# PumpMonitoring.net
KiCad netlist of a schematic drawn in EAGLE
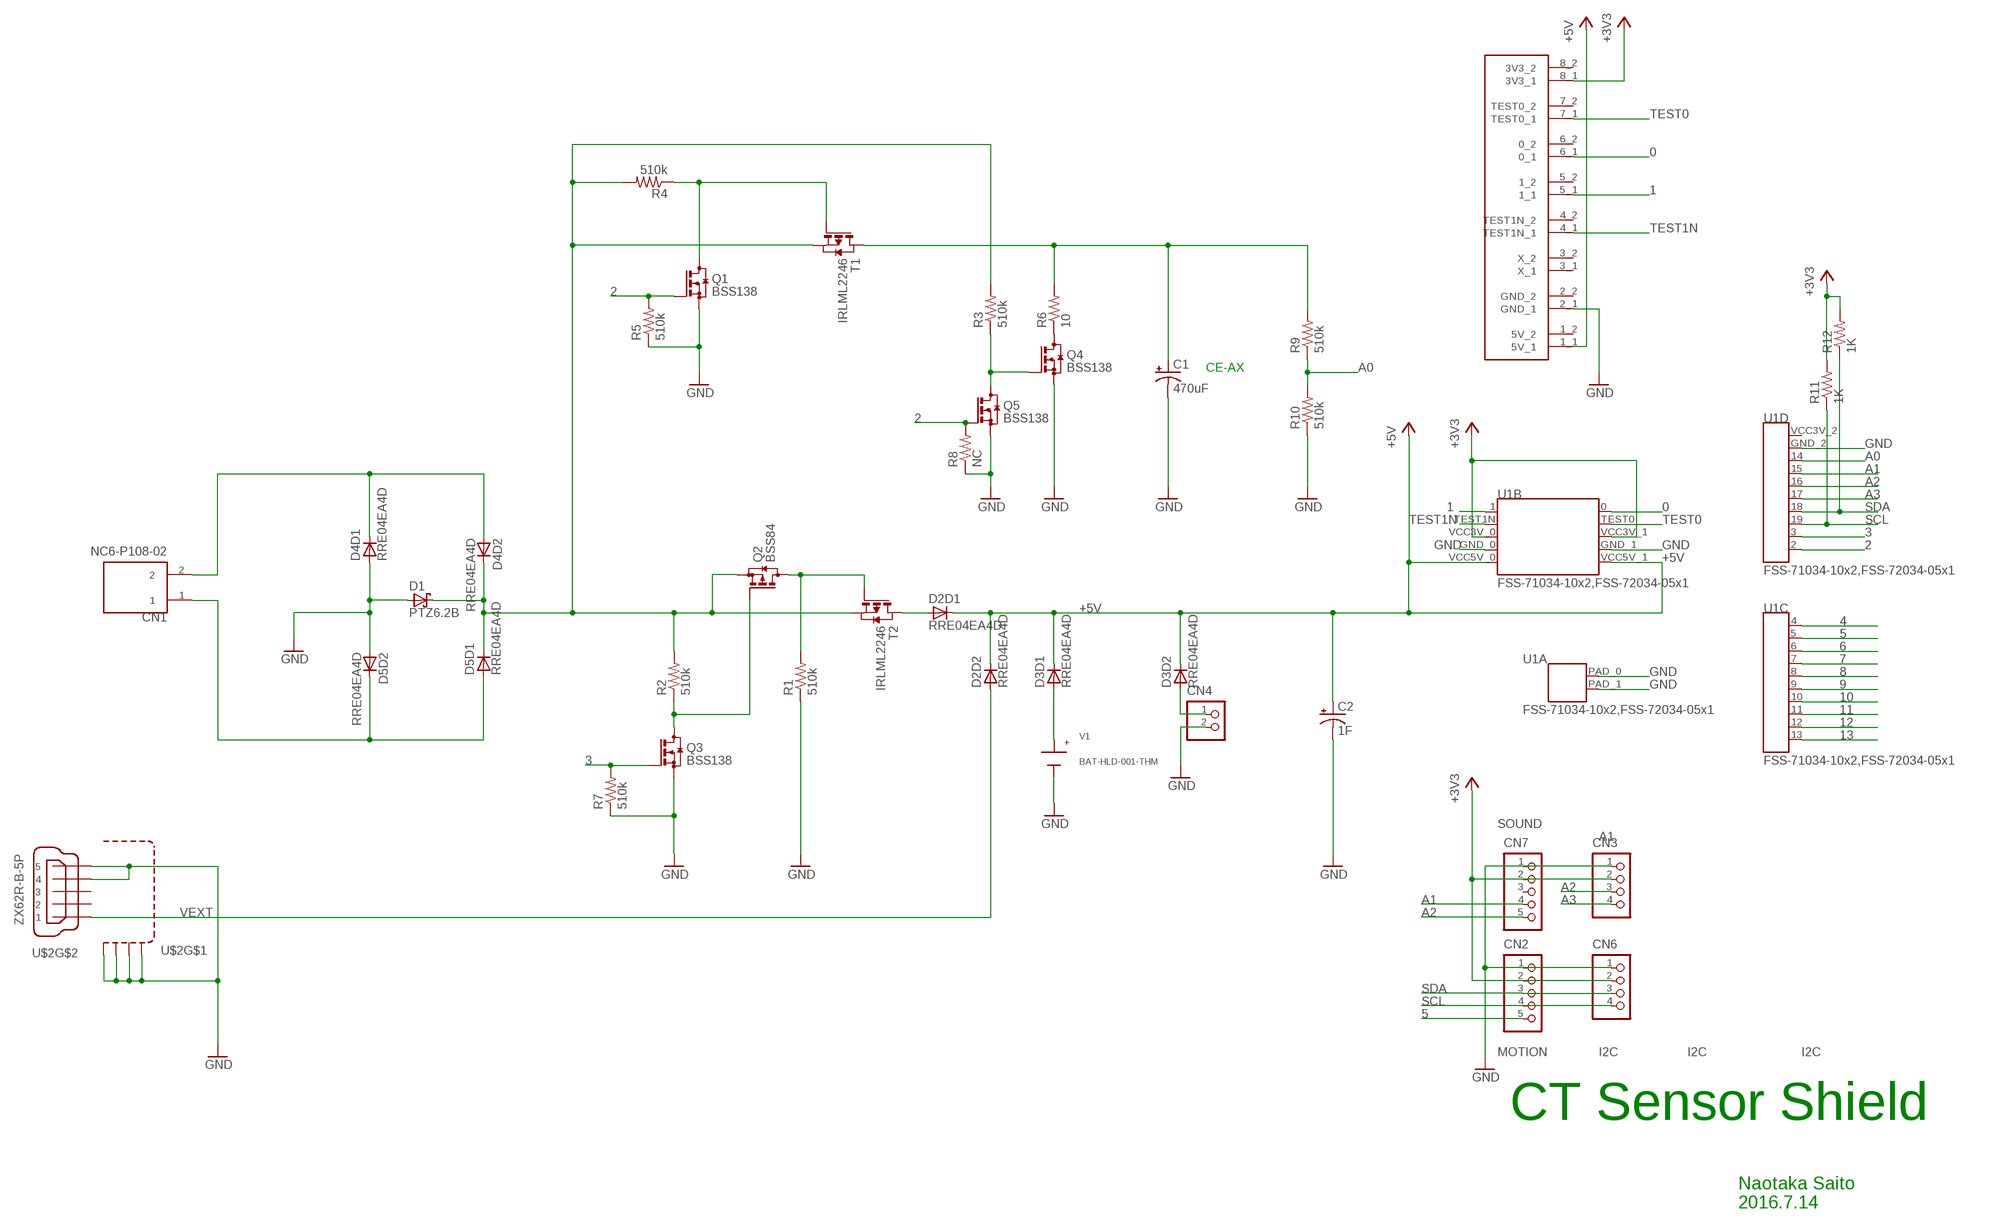
[diagram p0: schematic, sheet 1]

(export (version "E")
  (design (tool "Eeschema 10.0.6"))
  (components
    (comp (ref "C1")
      (value "470uF")
      (footprint "eagle-import:E5-10,5")
      (libsource (lib "eagle-import") (part "CPOL-USE5-10.5"))
    )
    (comp (ref "C2")
      (value "1F")
      (footprint "eagle-import:E5-20")
      (libsource (lib "eagle-import") (part "CPOL-USE5-20"))
    )
    (comp (ref "CN1")
      (value "NC6-P108-02")
      (footprint "eagle-import:2PIN")
      (libsource (lib "eagle-import") (part "TE-NC6-P108-02"))
    )
    (comp (ref "CN2")
      (value "B5B-PH-K-S")
      (footprint "eagle-import:B5B-PH-K-S")
      (libsource (lib "eagle-import") (part "B5B-PH-K-S"))
    )
    (comp (ref "CN3")
      (value "B4B-PH-K-S")
      (footprint "eagle-import:B4B-PH-K-S")
      (libsource (lib "eagle-import") (part "B4B-PH-K-S"))
    )
    (comp (ref "CN4")
      (value "B2B-PH-K-S")
      (footprint "eagle-import:B2B-PH-K-S")
      (libsource (lib "eagle-import") (part "B2B-PH-K-S"))
    )
    (comp (ref "CN6")
      (value "B4B-PH-K-S")
      (footprint "eagle-import:B4B-PH-K-S")
      (libsource (lib "eagle-import") (part "B4B-PH-K-S"))
    )
    (comp (ref "CN7")
      (value "B5B-PH-K-S")
      (footprint "eagle-import:B5B-PH-K-S")
      (libsource (lib "eagle-import") (part "B5B-PH-K-S"))
    )
    (comp (ref "D1")
      (value "PTZ6.2B")
      (footprint "eagle-import:DO214AC")
      (libsource (lib "eagle-import") (part "PTZXXB"))
    )
    (comp (ref "D2")
      (value "RRE04EA4D")
      (footprint "eagle-import:TSMD5")
      (libsource (lib "eagle-import") (part "RRE04EA4D"))
    )
    (comp (ref "D3")
      (value "RRE04EA4D")
      (footprint "eagle-import:TSMD5")
      (libsource (lib "eagle-import") (part "RRE04EA4D"))
    )
    (comp (ref "D4")
      (value "RRE04EA4D")
      (footprint "eagle-import:TSMD5")
      (libsource (lib "eagle-import") (part "RRE04EA4D"))
    )
    (comp (ref "D5")
      (value "RRE04EA4D")
      (footprint "eagle-import:TSMD5")
      (libsource (lib "eagle-import") (part "RRE04EA4D"))
    )
    (comp (ref "Q1")
      (value "BSS138")
      (footprint "eagle-import:SOT23")
      (libsource (lib "eagle-import") (part "BSS123"))
    )
    (comp (ref "Q2")
      (value "BSS84")
      (footprint "eagle-import:SOT23")
      (libsource (lib "eagle-import") (part "BSS84"))
    )
    (comp (ref "Q3")
      (value "BSS138")
      (footprint "eagle-import:SOT23")
      (libsource (lib "eagle-import") (part "BSS123"))
    )
    (comp (ref "Q4")
      (value "BSS138")
      (footprint "eagle-import:SOT23")
      (libsource (lib "eagle-import") (part "BSS123"))
    )
    (comp (ref "Q5")
      (value "BSS138")
      (footprint "eagle-import:SOT23")
      (libsource (lib "eagle-import") (part "BSS123"))
    )
    (comp (ref "R1")
      (value "510k")
      (footprint "eagle-import:R0603")
      (libsource (lib "eagle-import") (part "R-US_R0603"))
    )
    (comp (ref "R2")
      (value "510k")
      (footprint "eagle-import:R0603")
      (libsource (lib "eagle-import") (part "R-US_R0603"))
    )
    (comp (ref "R3")
      (value "510k")
      (footprint "eagle-import:R0603")
      (libsource (lib "eagle-import") (part "R-US_R0603"))
    )
    (comp (ref "R4")
      (value "510k")
      (footprint "eagle-import:R0603")
      (libsource (lib "eagle-import") (part "R-US_R0603"))
    )
    (comp (ref "R5")
      (value "510k")
      (footprint "eagle-import:R0603")
      (libsource (lib "eagle-import") (part "R-US_R0603"))
    )
    (comp (ref "R6")
      (value "10")
      (footprint "eagle-import:EZP")
      (libsource (lib "eagle-import") (part "MCR18"))
    )
    (comp (ref "R7")
      (value "510k")
      (footprint "eagle-import:R0603")
      (libsource (lib "eagle-import") (part "R-US_R0603"))
    )
    (comp (ref "R8")
      (value "NC")
      (footprint "eagle-import:R0603")
      (libsource (lib "eagle-import") (part "R-US_R0603"))
    )
    (comp (ref "R9")
      (value "510k")
      (footprint "eagle-import:R0603")
      (libsource (lib "eagle-import") (part "R-US_R0603"))
    )
    (comp (ref "R10")
      (value "510k")
      (footprint "eagle-import:R0603")
      (libsource (lib "eagle-import") (part "R-US_R0603"))
    )
    (comp (ref "R11")
      (value "1K")
      (footprint "eagle-import:R0603")
      (libsource (lib "eagle-import") (part "R-US_R0603"))
    )
    (comp (ref "R12")
      (value "1K")
      (footprint "eagle-import:R0603")
      (libsource (lib "eagle-import") (part "R-US_R0603"))
    )
    (comp (ref "T1")
      (value "IRLML2246")
      (footprint "eagle-import:SOT-23")
      (libsource (lib "eagle-import") (part "PMOSSOT23"))
    )
    (comp (ref "T2")
      (value "IRLML2246")
      (footprint "eagle-import:SOT-23")
      (libsource (lib "eagle-import") (part "PMOSSOT23"))
    )
    (comp (ref "U$1")
      (value "XB-1-X")
      (footprint "eagle-import:XB-1-X")
      (libsource (lib "eagle-import") (part "XB-1-X"))
    )
    (comp (ref "U$2")
      (value "ZX62R-B-5P")
      (footprint "eagle-import:ZX62R-B-5P")
      (libsource (lib "eagle-import") (part "MICRO-USB-SHIELD-ZX62R-B-5P"))
    )
    (comp (ref "U1")
      (value "FSS-71034-10x2,FSS-72034-05x1")
      (footprint "eagle-import:LAZURITE920J")
      (libsource (lib "eagle-import") (part "LAZURITE920JLAZURITE920J"))
    )
    (comp (ref "V1")
      (value "BAT-HLD-001-THM")
      (footprint "eagle-import:CR2032")
      (libsource (lib "eagle-import") (part "BAT-HLD-001-THM"))
    )
  )
  (nets
    (net (code "1") (name "+3V3") (class "Default")
      (node (ref "CN2") (pin "2") (pinfunction "2_2") (pintype "passive"))
      (node (ref "CN3") (pin "2") (pinfunction "2_2") (pintype "passive"))
      (node (ref "CN6") (pin "2") (pinfunction "2_2") (pintype "passive"))
      (node (ref "CN7") (pin "2") (pinfunction "2_2") (pintype "passive"))
      (node (ref "R11") (pin "2") (pinfunction "2_2") (pintype "passive"))
      (node (ref "R12") (pin "2") (pinfunction "2_2") (pintype "passive"))
      (node (ref "U$1") (pin "8_1") (pinfunction "3V3_1_8_1") (pintype "bidirectional"))
      (node (ref "U1") (pin "VCC3V_0") (pinfunction "VCC3V_0_VCC3V_0") (pintype "passive"))
      (node (ref "U1") (pin "VCC3V_1") (pinfunction "VCC3V_1_VCC3V_1") (pintype "passive"))
    )
    (net (code "2") (name "+5V") (class "Default")
      (node (ref "C2") (pin "+") (pinfunction "+_+") (pintype "passive"))
      (node (ref "D2") (pin "4") (pinfunction "C_4") (pintype "passive"))
      (node (ref "D2") (pin "5") (pinfunction "C_5") (pintype "passive"))
      (node (ref "D3") (pin "4") (pinfunction "C_4") (pintype "passive"))
      (node (ref "D3") (pin "5") (pinfunction "C_5") (pintype "passive"))
      (node (ref "U$1") (pin "1_1") (pinfunction "5V_1_1_1") (pintype "bidirectional"))
      (node (ref "U1") (pin "VCC5V_0") (pinfunction "VCC5V_0_VCC5V_0") (pintype "passive"))
      (node (ref "U1") (pin "VCC5V_1") (pinfunction "VCC5V_1_VCC5V_1") (pintype "passive"))
    )
    (net (code "3") (name "/0") (class "Default")
      (node (ref "U$1") (pin "6_1") (pinfunction "0_1_6_1") (pintype "bidirectional"))
      (node (ref "U1") (pin "0") (pinfunction "0_0") (pintype "passive"))
    )
    (net (code "4") (name "/1") (class "Default")
      (node (ref "U$1") (pin "5_1") (pinfunction "1_1_5_1") (pintype "bidirectional"))
      (node (ref "U1") (pin "1") (pinfunction "1_1") (pintype "passive"))
    )
    (net (code "5") (name "/2") (class "Default")
      (node (ref "Q1") (pin "1") (pinfunction "G_1") (pintype "passive"))
      (node (ref "Q5") (pin "1") (pinfunction "G_1") (pintype "passive"))
      (node (ref "R5") (pin "2") (pinfunction "2_2") (pintype "passive"))
      (node (ref "R8") (pin "2") (pinfunction "2_2") (pintype "passive"))
      (node (ref "U1") (pin "2") (pinfunction "2_2") (pintype "passive"))
    )
    (net (code "6") (name "/3") (class "Default")
      (node (ref "Q3") (pin "1") (pinfunction "G_1") (pintype "passive"))
      (node (ref "R7") (pin "2") (pinfunction "2_2") (pintype "passive"))
      (node (ref "U1") (pin "3") (pinfunction "3_3") (pintype "passive"))
    )
    (net (code "7") (name "/4") (class "Default")
      (node (ref "U1") (pin "4") (pinfunction "4_4") (pintype "passive"))
    )
    (net (code "8") (name "/5") (class "Default")
      (node (ref "CN2") (pin "5") (pinfunction "5_5") (pintype "passive"))
      (node (ref "U1") (pin "5") (pinfunction "5_5") (pintype "passive"))
    )
    (net (code "9") (name "/6") (class "Default")
      (node (ref "U1") (pin "6") (pinfunction "6_6") (pintype "passive"))
    )
    (net (code "10") (name "/7") (class "Default")
      (node (ref "U1") (pin "7") (pinfunction "7_7") (pintype "passive"))
    )
    (net (code "11") (name "/8") (class "Default")
      (node (ref "U1") (pin "8") (pinfunction "8_8") (pintype "passive"))
    )
    (net (code "12") (name "/9") (class "Default")
      (node (ref "U1") (pin "9") (pinfunction "9_9") (pintype "passive"))
    )
    (net (code "13") (name "/10") (class "Default")
      (node (ref "U1") (pin "10") (pinfunction "10_10") (pintype "passive"))
    )
    (net (code "14") (name "/11") (class "Default")
      (node (ref "U1") (pin "11") (pinfunction "11_11") (pintype "passive"))
    )
    (net (code "15") (name "/12") (class "Default")
      (node (ref "U1") (pin "12") (pinfunction "12_12") (pintype "passive"))
    )
    (net (code "16") (name "/13") (class "Default")
      (node (ref "U1") (pin "13") (pinfunction "13_13") (pintype "passive"))
    )
    (net (code "17") (name "/A0") (class "Default")
      (node (ref "R10") (pin "2") (pinfunction "2_2") (pintype "passive"))
      (node (ref "R9") (pin "1") (pinfunction "1_1") (pintype "passive"))
      (node (ref "U1") (pin "14") (pinfunction "14_14") (pintype "passive"))
    )
    (net (code "18") (name "/A1") (class "Default")
      (node (ref "CN7") (pin "4") (pinfunction "4_4") (pintype "passive"))
      (node (ref "U1") (pin "15") (pinfunction "15_15") (pintype "passive"))
    )
    (net (code "19") (name "/A2") (class "Default")
      (node (ref "CN3") (pin "3") (pinfunction "3_3") (pintype "passive"))
      (node (ref "CN7") (pin "5") (pinfunction "5_5") (pintype "passive"))
      (node (ref "U1") (pin "16") (pinfunction "16_16") (pintype "passive"))
    )
    (net (code "20") (name "/A3") (class "Default")
      (node (ref "CN3") (pin "4") (pinfunction "4_4") (pintype "passive"))
      (node (ref "U1") (pin "17") (pinfunction "17_17") (pintype "passive"))
    )
    (net (code "21") (name "/SCL") (class "Default")
      (node (ref "CN2") (pin "4") (pinfunction "4_4") (pintype "passive"))
      (node (ref "CN6") (pin "4") (pinfunction "4_4") (pintype "passive"))
      (node (ref "R11") (pin "1") (pinfunction "1_1") (pintype "passive"))
      (node (ref "U1") (pin "19") (pinfunction "19_19") (pintype "passive"))
    )
    (net (code "22") (name "/SDA") (class "Default")
      (node (ref "CN2") (pin "3") (pinfunction "3_3") (pintype "passive"))
      (node (ref "CN6") (pin "3") (pinfunction "3_3") (pintype "passive"))
      (node (ref "R12") (pin "1") (pinfunction "1_1") (pintype "passive"))
      (node (ref "U1") (pin "18") (pinfunction "18_18") (pintype "passive"))
    )
    (net (code "23") (name "/TEST0") (class "Default")
      (node (ref "U$1") (pin "7_1") (pinfunction "TEST0_1_7_1") (pintype "bidirectional"))
      (node (ref "U1") (pin "TEST0") (pinfunction "TEST0_TEST0") (pintype "passive"))
    )
    (net (code "24") (name "/TEST1N") (class "Default")
      (node (ref "U$1") (pin "4_1") (pinfunction "TEST1N_1_4_1") (pintype "bidirectional"))
      (node (ref "U1") (pin "TEST1N") (pinfunction "TEST1N_TEST1N") (pintype "passive"))
    )
    (net (code "25") (name "/VEXT") (class "Default")
      (node (ref "D2") (pin "3") (pinfunction "A_3") (pintype "passive"))
      (node (ref "U$2") (pin "1") (pinfunction "1_1") (pintype "input"))
    )
    (net (code "26") (name "GND") (class "Default")
      (node (ref "C1") (pin "-") (pinfunction "-_-") (pintype "passive"))
      (node (ref "C2") (pin "-") (pinfunction "-_-") (pintype "passive"))
      (node (ref "CN2") (pin "1") (pinfunction "1_1") (pintype "passive"))
      (node (ref "CN3") (pin "1") (pinfunction "1_1") (pintype "passive"))
      (node (ref "CN4") (pin "2") (pinfunction "2_2") (pintype "passive"))
      (node (ref "CN6") (pin "1") (pinfunction "1_1") (pintype "passive"))
      (node (ref "CN7") (pin "1") (pinfunction "1_1") (pintype "passive"))
      (node (ref "D1") (pin "A") (pinfunction "A_A") (pintype "passive"))
      (node (ref "D4") (pin "1") (pinfunction "A_1") (pintype "passive"))
      (node (ref "D5") (pin "3") (pinfunction "A_3") (pintype "passive"))
      (node (ref "Q1") (pin "2") (pinfunction "S_2") (pintype "passive"))
      (node (ref "Q3") (pin "2") (pinfunction "S_2") (pintype "passive"))
      (node (ref "Q4") (pin "2") (pinfunction "S_2") (pintype "passive"))
      (node (ref "Q5") (pin "2") (pinfunction "S_2") (pintype "passive"))
      (node (ref "R1") (pin "1") (pinfunction "1_1") (pintype "passive"))
      (node (ref "R10") (pin "1") (pinfunction "1_1") (pintype "passive"))
      (node (ref "R5") (pin "1") (pinfunction "1_1") (pintype "passive"))
      (node (ref "R7") (pin "1") (pinfunction "1_1") (pintype "passive"))
      (node (ref "R8") (pin "1") (pinfunction "1_1") (pintype "passive"))
      (node (ref "U$1") (pin "2_1") (pinfunction "GND_1_2_1") (pintype "bidirectional"))
      (node (ref "U$2") (pin "4") (pinfunction "4_4") (pintype "input"))
      (node (ref "U$2") (pin "5") (pinfunction "5_5") (pintype "input"))
      (node (ref "U$2") (pin "M1") (pinfunction "S1_M1") (pintype "passive"))
      (node (ref "U$2") (pin "M2") (pinfunction "S2_M2") (pintype "passive"))
      (node (ref "U$2") (pin "M3") (pinfunction "S3_M3") (pintype "passive"))
      (node (ref "U$2") (pin "M4") (pinfunction "S4_M4") (pintype "passive"))
      (node (ref "U1") (pin "GND_0") (pinfunction "GND_0_GND_0") (pintype "passive"))
      (node (ref "U1") (pin "GND_1") (pinfunction "GND_1_GND_1") (pintype "passive"))
      (node (ref "U1") (pin "GND_2") (pinfunction "GND_2_GND_2") (pintype "passive"))
      (node (ref "U1") (pin "PAD_0") (pinfunction "PAD_0_PAD_0") (pintype "passive"))
      (node (ref "U1") (pin "PAD_1") (pinfunction "PAD_1_PAD_1") (pintype "passive"))
      (node (ref "V1") (pin "GND") (pinfunction "GND_GND") (pintype "power_in"))
    )
    (net (code "27") (name "Net-(D2A-A)") (class "Default")
      (node (ref "D2") (pin "1") (pinfunction "A_1") (pintype "passive"))
      (node (ref "T2") (pin "1") (pinfunction "D_1") (pintype "passive"))
    )
    (net (code "28") (name "Net-(D3A-A)") (class "Default")
      (node (ref "D3") (pin "1") (pinfunction "A_1") (pintype "passive"))
      (node (ref "V1") (pin "VDD1") (pinfunction "VDD_VDD1") (pintype "power_in"))
      (node (ref "V1") (pin "VDD2") (pinfunction "VDD_VDD2") (pintype "power_in"))
      (node (ref "V1") (pin "VDD3") (pinfunction "VDD_VDD3") (pintype "power_in"))
      (node (ref "V1") (pin "VDD4") (pinfunction "VDD_VDD4") (pintype "power_in"))
    )
    (net (code "29") (name "Net-(D3B-A)") (class "Default")
      (node (ref "CN4") (pin "1") (pinfunction "1_1") (pintype "passive"))
      (node (ref "D3") (pin "3") (pinfunction "A_3") (pintype "passive"))
    )
    (net (code "30") (name "Net-(D4A-C)") (class "Default")
      (node (ref "CN1") (pin "2") (pinfunction "2_2") (pintype "passive"))
      (node (ref "D4") (pin "3") (pinfunction "A_3") (pintype "passive"))
      (node (ref "D4") (pin "5") (pinfunction "C_5") (pintype "passive"))
    )
    (net (code "31") (name "Net-(D4B-C)") (class "Default")
      (node (ref "D1") (pin "C") (pinfunction "C_C") (pintype "passive"))
      (node (ref "D4") (pin "4") (pinfunction "C_4") (pintype "passive"))
      (node (ref "D5") (pin "5") (pinfunction "C_5") (pintype "passive"))
      (node (ref "Q2") (pin "2") (pinfunction "S_2") (pintype "passive"))
      (node (ref "R2") (pin "2") (pinfunction "2_2") (pintype "passive"))
      (node (ref "R3") (pin "2") (pinfunction "2_2") (pintype "passive"))
      (node (ref "R4") (pin "2") (pinfunction "2_2") (pintype "passive"))
      (node (ref "T1") (pin "2") (pinfunction "S_2") (pintype "passive"))
      (node (ref "T2") (pin "2") (pinfunction "S_2") (pintype "passive"))
    )
    (net (code "32") (name "Net-(D5A-A)") (class "Default")
      (node (ref "CN1") (pin "1") (pinfunction "1_1") (pintype "passive"))
      (node (ref "D5") (pin "1") (pinfunction "A_1") (pintype "passive"))
      (node (ref "D5") (pin "4") (pinfunction "C_4") (pintype "passive"))
    )
    (net (code "33") (name "Net-(Q1-D)") (class "Default")
      (node (ref "Q1") (pin "3") (pinfunction "D_3") (pintype "passive"))
      (node (ref "R4") (pin "1") (pinfunction "1_1") (pintype "passive"))
      (node (ref "T1") (pin "3") (pinfunction "G_3") (pintype "passive"))
    )
    (net (code "34") (name "Net-(Q2-D)") (class "Default")
      (node (ref "Q2") (pin "3") (pinfunction "D_3") (pintype "passive"))
      (node (ref "R1") (pin "2") (pinfunction "2_2") (pintype "passive"))
      (node (ref "T2") (pin "3") (pinfunction "G_3") (pintype "passive"))
    )
    (net (code "35") (name "Net-(Q2-G)") (class "Default")
      (node (ref "Q2") (pin "1") (pinfunction "G_1") (pintype "passive"))
      (node (ref "Q3") (pin "3") (pinfunction "D_3") (pintype "passive"))
      (node (ref "R2") (pin "1") (pinfunction "1_1") (pintype "passive"))
    )
    (net (code "36") (name "Net-(Q4-D)") (class "Default")
      (node (ref "Q4") (pin "3") (pinfunction "D_3") (pintype "passive"))
      (node (ref "R6") (pin "1") (pinfunction "1_1") (pintype "passive"))
    )
    (net (code "37") (name "Net-(Q4-G)") (class "Default")
      (node (ref "Q4") (pin "1") (pinfunction "G_1") (pintype "passive"))
      (node (ref "Q5") (pin "3") (pinfunction "D_3") (pintype "passive"))
      (node (ref "R3") (pin "1") (pinfunction "1_1") (pintype "passive"))
    )
    (net (code "38") (name "Net-(T1-D)") (class "Default")
      (node (ref "C1") (pin "+") (pinfunction "+_+") (pintype "passive"))
      (node (ref "R6") (pin "2") (pinfunction "2_2") (pintype "passive"))
      (node (ref "R9") (pin "2") (pinfunction "2_2") (pintype "passive"))
      (node (ref "T1") (pin "1") (pinfunction "D_1") (pintype "passive"))
    )
    (net (code "39") (name "unconnected-(CN7-Pad3)") (class "Default")
      (node (ref "CN7") (pin "3") (pinfunction "3_3") (pintype "passive"))
    )
    (net (code "40") (name "unconnected-(U$1-0_2-Pad6_2)") (class "Default")
      (node (ref "U$1") (pin "6_2") (pinfunction "0_2_6_2") (pintype "bidirectional"))
    )
    (net (code "41") (name "unconnected-(U$1-1_2-Pad5_2)") (class "Default")
      (node (ref "U$1") (pin "5_2") (pinfunction "1_2_5_2") (pintype "bidirectional"))
    )
    (net (code "42") (name "unconnected-(U$1-3V3_2-Pad8_2)") (class "Default")
      (node (ref "U$1") (pin "8_2") (pinfunction "3V3_2_8_2") (pintype "bidirectional"))
    )
    (net (code "43") (name "unconnected-(U$1-5V_2-Pad1_2)") (class "Default")
      (node (ref "U$1") (pin "1_2") (pinfunction "5V_2_1_2") (pintype "bidirectional"))
    )
    (net (code "44") (name "unconnected-(U$1-GND_2-Pad2_2)") (class "Default")
      (node (ref "U$1") (pin "2_2") (pinfunction "GND_2_2_2") (pintype "bidirectional"))
    )
    (net (code "45") (name "unconnected-(U$1-TEST0_2-Pad7_2)") (class "Default")
      (node (ref "U$1") (pin "7_2") (pinfunction "TEST0_2_7_2") (pintype "bidirectional"))
    )
    (net (code "46") (name "unconnected-(U$1-TEST1N_2-Pad4_2)") (class "Default")
      (node (ref "U$1") (pin "4_2") (pinfunction "TEST1N_2_4_2") (pintype "bidirectional"))
    )
    (net (code "47") (name "unconnected-(U$1-X_1-Pad3_1)") (class "Default")
      (node (ref "U$1") (pin "3_1") (pinfunction "X_1_3_1") (pintype "bidirectional"))
    )
    (net (code "48") (name "unconnected-(U$1-X_2-Pad3_2)") (class "Default")
      (node (ref "U$1") (pin "3_2") (pinfunction "X_2_3_2") (pintype "bidirectional"))
    )
    (net (code "49") (name "unconnected-(U$2-Pad2)") (class "Default")
      (node (ref "U$2") (pin "2") (pinfunction "2_2") (pintype "input"))
    )
    (net (code "50") (name "unconnected-(U$2-Pad3)") (class "Default")
      (node (ref "U$2") (pin "3") (pinfunction "3_3") (pintype "input"))
    )
    (net (code "51") (name "unconnected-(U1-PadVCC3V_2)") (class "Default")
      (node (ref "U1") (pin "VCC3V_2") (pinfunction "VCC3V_2_VCC3V_2") (pintype "passive"))
    )
  )
)
